# vco.net
KiCad netlist of a schematic drawn in EAGLE
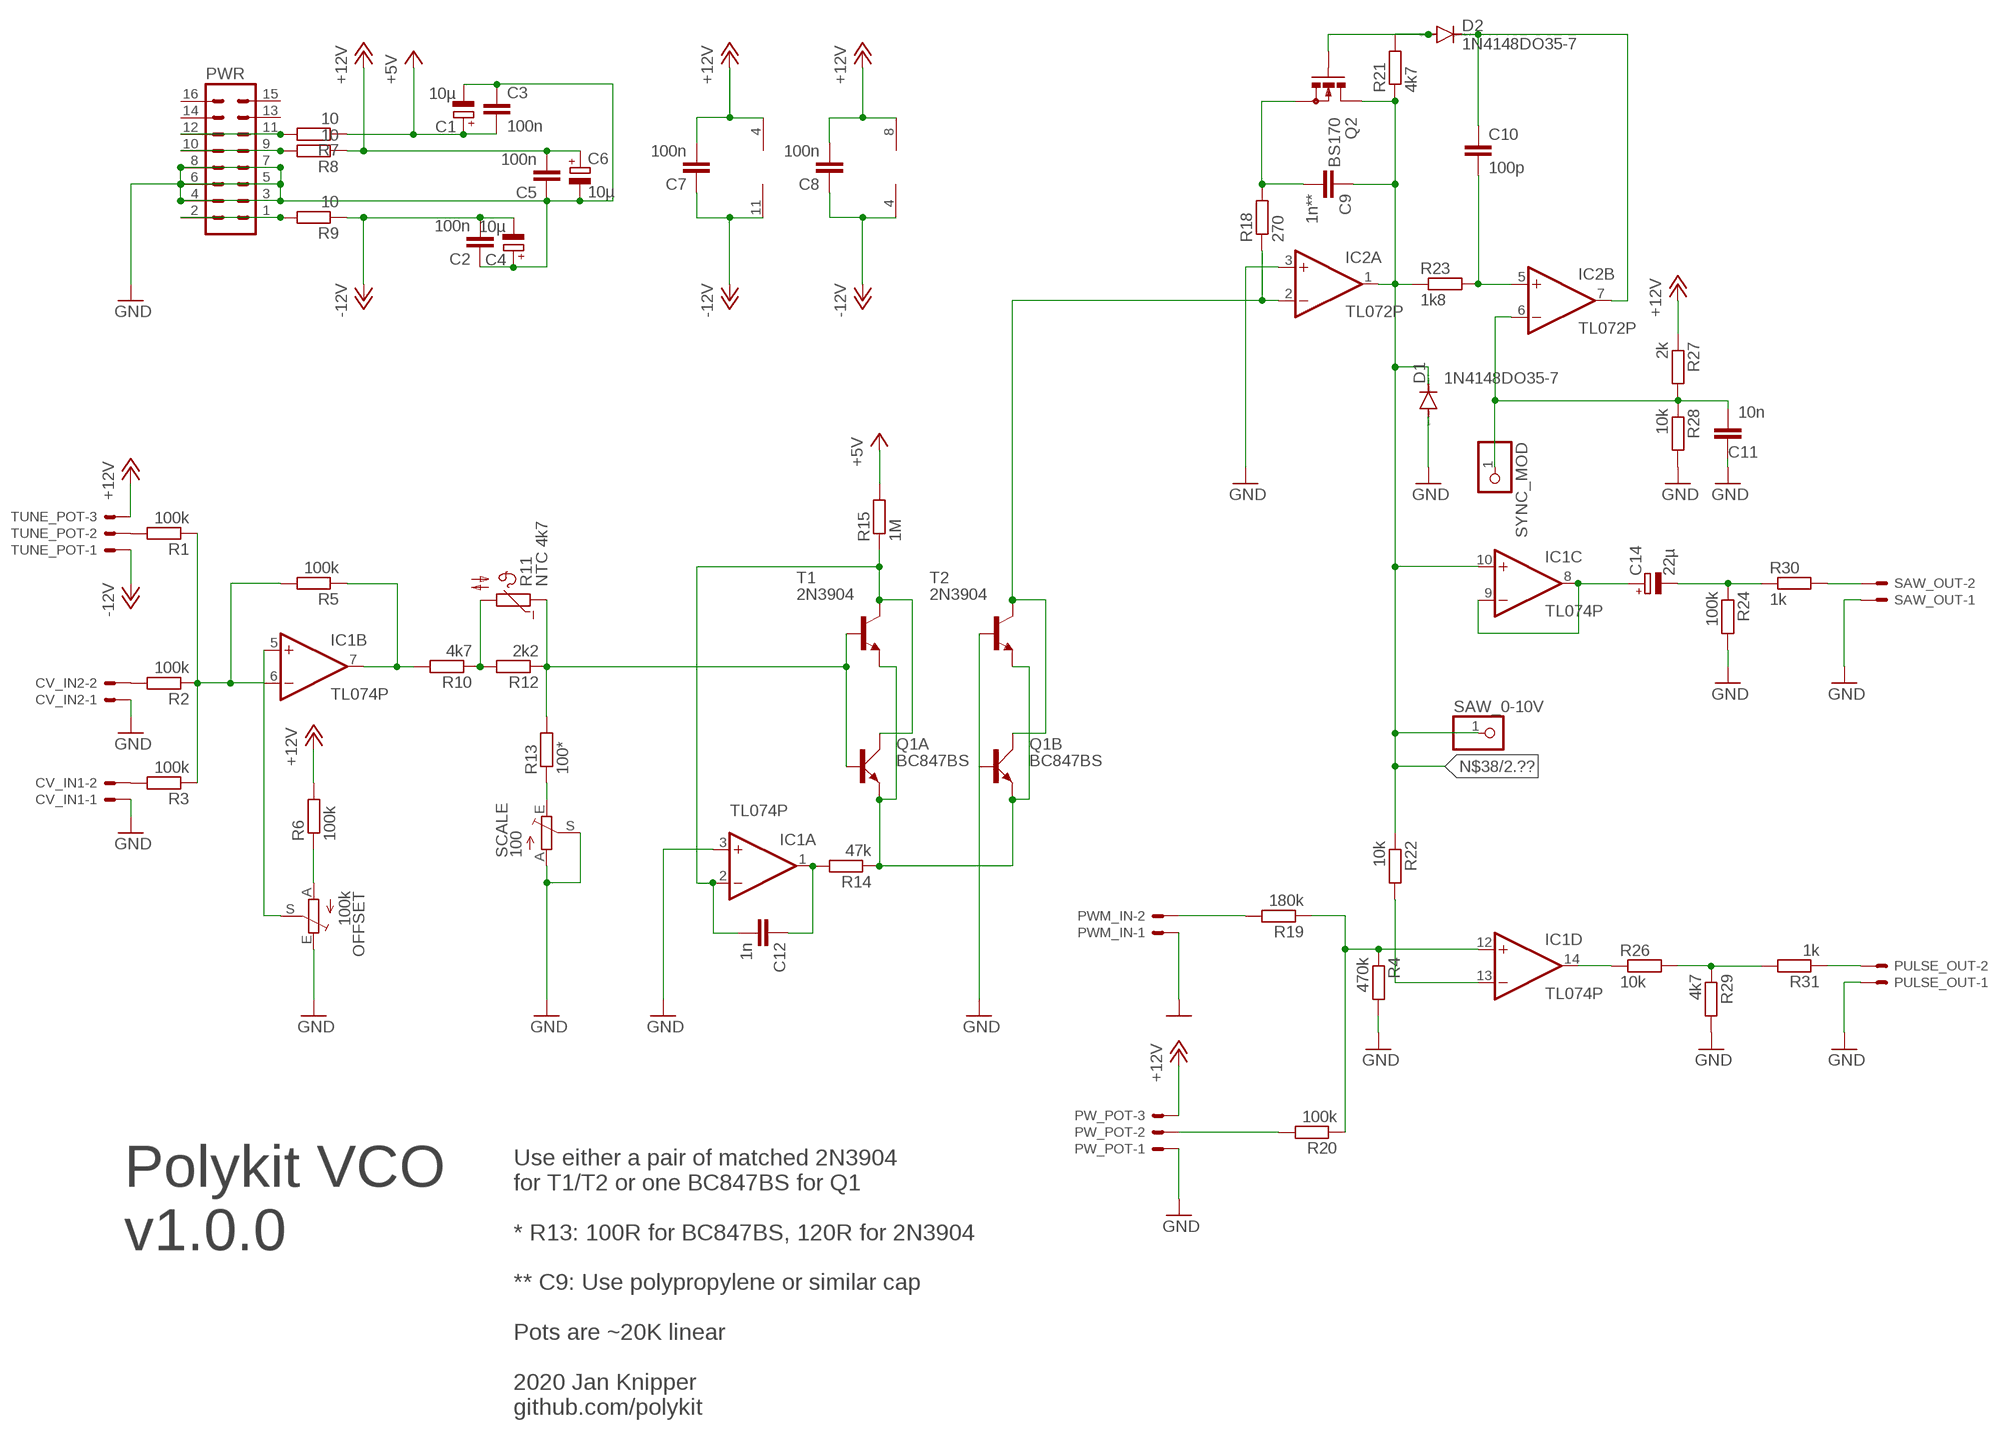
[diagram p0: schematic, sheet 1]
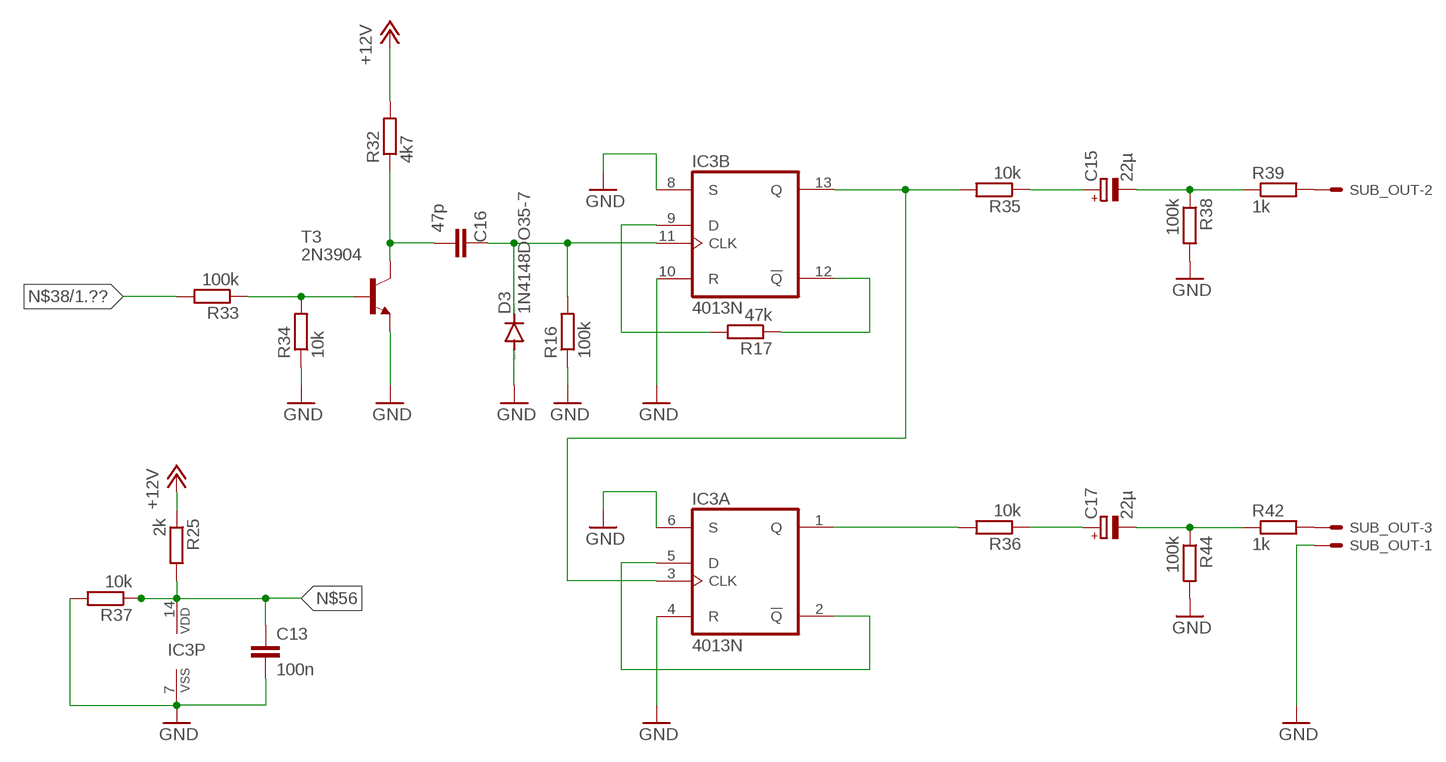
[diagram p1: schematic, sheet 2]

(export (version "E")
  (design (tool "Eeschema 10.0.6"))
  (components
    (comp (ref "C1")
      (value "10µ")
      (footprint "eagle-import:E2,5-5")
      (libsource (lib "eagle-import") (part "CPOL-EUE2.5-5"))
    )
    (comp (ref "C2")
      (value "100n")
      (footprint "eagle-import:C050-030X075")
      (libsource (lib "eagle-import") (part "C-EU050-030X075"))
    )
    (comp (ref "C3")
      (value "100n")
      (footprint "eagle-import:C050-030X075")
      (libsource (lib "eagle-import") (part "C-EU050-030X075"))
    )
    (comp (ref "C4")
      (value "10µ")
      (footprint "eagle-import:E2,5-5")
      (libsource (lib "eagle-import") (part "CPOL-EUE2.5-5"))
    )
    (comp (ref "C5")
      (value "100n")
      (footprint "eagle-import:C050-030X075")
      (libsource (lib "eagle-import") (part "C-EU050-030X075"))
    )
    (comp (ref "C6")
      (value "10µ")
      (footprint "eagle-import:E2,5-5")
      (libsource (lib "eagle-import") (part "CPOL-EUE2.5-5"))
    )
    (comp (ref "C7")
      (value "100n")
      (footprint "eagle-import:C050-030X075")
      (libsource (lib "eagle-import") (part "C-EU050-030X075"))
    )
    (comp (ref "C8")
      (value "100n")
      (footprint "eagle-import:C050-030X075")
      (libsource (lib "eagle-import") (part "C-EU050-030X075"))
    )
    (comp (ref "C9")
      (value "1n**")
      (footprint "eagle-import:C050-030X075")
      (libsource (lib "eagle-import") (part "C-EU050-030X075"))
    )
    (comp (ref "C10")
      (value "100p")
      (footprint "eagle-import:C050-030X075")
      (libsource (lib "eagle-import") (part "C-EU050-030X075"))
    )
    (comp (ref "C11")
      (value "10n")
      (footprint "eagle-import:C050-030X075")
      (libsource (lib "eagle-import") (part "C-EU050-030X075"))
    )
    (comp (ref "C12")
      (value "1n")
      (footprint "eagle-import:C050-024X044")
      (libsource (lib "eagle-import") (part "C-EU050-024X044"))
    )
    (comp (ref "C14")
      (value "22µ")
      (footprint "eagle-import:E2,5-5")
      (libsource (lib "eagle-import") (part "CPOL-EUE2.5-5"))
    )
    (comp (ref "CV_IN1")
      (value "22-23-2021")
      (footprint "eagle-import:22-23-2021")
      (fields (field (name "MF") "MOLEX"))
      (libsource (lib "eagle-import") (part "22-23-2021"))
    )
    (comp (ref "CV_IN2")
      (value "22-23-2021")
      (footprint "eagle-import:22-23-2021")
      (fields (field (name "MF") "MOLEX"))
      (libsource (lib "eagle-import") (part "22-23-2021"))
    )
    (comp (ref "D1")
      (value "1N4148DO35-7")
      (footprint "eagle-import:DO35-7")
      (libsource (lib "eagle-import") (part "1N4148DO35-7"))
    )
    (comp (ref "D2")
      (value "1N4148DO35-7")
      (footprint "eagle-import:DO35-7")
      (libsource (lib "eagle-import") (part "1N4148DO35-7"))
    )
    (comp (ref "IC1")
      (value "TL074P")
      (footprint "eagle-import:DIL14")
      (libsource (lib "eagle-import") (part "TL074P"))
    )
    (comp (ref "IC2")
      (value "TL072P")
      (footprint "eagle-import:DIL08")
      (libsource (lib "eagle-import") (part "TL072P"))
    )
    (comp (ref "OFFSET")
      (value "100k")
      (footprint "eagle-import:S64YW")
      (libsource (lib "eagle-import") (part "TRIM_1234-S64YW"))
    )
    (comp (ref "PULSE_OUT")
      (value "22-23-2021")
      (footprint "eagle-import:22-23-2021")
      (fields (field (name "MF") "MOLEX"))
      (libsource (lib "eagle-import") (part "22-23-2021"))
    )
    (comp (ref "PWM_IN")
      (value "22-23-2021")
      (footprint "eagle-import:22-23-2021")
      (fields (field (name "MF") "MOLEX"))
      (libsource (lib "eagle-import") (part "22-23-2021"))
    )
    (comp (ref "PWR")
      (value "ML16")
      (footprint "eagle-import:ML16")
      (libsource (lib "eagle-import") (part "ML16"))
    )
    (comp (ref "PW_POT")
      (value "22-23-2031")
      (footprint "eagle-import:22-23-2031")
      (fields (field (name "MF") "MOLEX"))
      (libsource (lib "eagle-import") (part "22-23-2031"))
    )
    (comp (ref "Q1")
      (value "BC847BS")
      (footprint "eagle-import:SOT363_PHILIPS")
      (libsource (lib "eagle-import") (part "BC847BS"))
    )
    (comp (ref "Q2")
      (value "BS170")
      (footprint "eagle-import:SOT54E")
      (libsource (lib "eagle-import") (part "BS170"))
    )
    (comp (ref "R1")
      (value "100k")
      (footprint "eagle-import:0207_7")
      (libsource (lib "eagle-import") (part "R-EU_0207/7"))
    )
    (comp (ref "R2")
      (value "100k")
      (footprint "eagle-import:0207_7")
      (libsource (lib "eagle-import") (part "R-EU_0207/7"))
    )
    (comp (ref "R3")
      (value "100k")
      (footprint "eagle-import:0207_7")
      (libsource (lib "eagle-import") (part "R-EU_0207/7"))
    )
    (comp (ref "R4")
      (value "470k")
      (footprint "eagle-import:0207_7")
      (libsource (lib "eagle-import") (part "R-EU_0207/7"))
    )
    (comp (ref "R5")
      (value "100k")
      (footprint "eagle-import:0207_7")
      (libsource (lib "eagle-import") (part "R-EU_0207/7"))
    )
    (comp (ref "R6")
      (value "100k")
      (footprint "eagle-import:0207_7")
      (libsource (lib "eagle-import") (part "R-EU_0207/7"))
    )
    (comp (ref "R7")
      (value "10")
      (footprint "eagle-import:0207_7")
      (libsource (lib "eagle-import") (part "R-EU_0207/7"))
    )
    (comp (ref "R8")
      (value "10")
      (footprint "eagle-import:0207_7")
      (libsource (lib "eagle-import") (part "R-EU_0207/7"))
    )
    (comp (ref "R9")
      (value "10")
      (footprint "eagle-import:0207_7")
      (libsource (lib "eagle-import") (part "R-EU_0207/7"))
    )
    (comp (ref "R10")
      (value "4k7")
      (footprint "eagle-import:0207_7")
      (libsource (lib "eagle-import") (part "R-EU_0207/7"))
    )
    (comp (ref "R11")
      (value "NTC 4k7")
      (footprint "eagle-import:P640")
      (libsource (lib "eagle-import") (part "NTC640"))
    )
    (comp (ref "R12")
      (value "2k2")
      (footprint "eagle-import:0207_7")
      (libsource (lib "eagle-import") (part "R-EU_0207/7"))
    )
    (comp (ref "R13")
      (value "100*")
      (footprint "eagle-import:0207_7")
      (libsource (lib "eagle-import") (part "R-EU_0207/7"))
    )
    (comp (ref "R14")
      (value "47k")
      (footprint "eagle-import:0207_7")
      (libsource (lib "eagle-import") (part "R-EU_0207/7"))
    )
    (comp (ref "R15")
      (value "1M")
      (footprint "eagle-import:0207_7")
      (libsource (lib "eagle-import") (part "R-EU_0207/7"))
    )
    (comp (ref "R18")
      (value "270")
      (footprint "eagle-import:0207_7")
      (libsource (lib "eagle-import") (part "R-EU_0207/7"))
    )
    (comp (ref "R19")
      (value "180k")
      (footprint "eagle-import:0207_7")
      (libsource (lib "eagle-import") (part "R-EU_0207/7"))
    )
    (comp (ref "R20")
      (value "100k")
      (footprint "eagle-import:0207_7")
      (libsource (lib "eagle-import") (part "R-EU_0207/7"))
    )
    (comp (ref "R21")
      (value "4k7")
      (footprint "eagle-import:0207_7")
      (libsource (lib "eagle-import") (part "R-EU_0207/7"))
    )
    (comp (ref "R22")
      (value "10k")
      (footprint "eagle-import:0207_7")
      (libsource (lib "eagle-import") (part "R-EU_0207/7"))
    )
    (comp (ref "R23")
      (value "1k8")
      (footprint "eagle-import:0207_7")
      (libsource (lib "eagle-import") (part "R-EU_0207/7"))
    )
    (comp (ref "R24")
      (value "100k")
      (footprint "eagle-import:0207_7")
      (libsource (lib "eagle-import") (part "R-EU_0207/7"))
    )
    (comp (ref "R26")
      (value "10k")
      (footprint "eagle-import:0207_7")
      (libsource (lib "eagle-import") (part "R-EU_0207/7"))
    )
    (comp (ref "R27")
      (value "2k")
      (footprint "eagle-import:0207_7")
      (libsource (lib "eagle-import") (part "R-EU_0207/7"))
    )
    (comp (ref "R28")
      (value "10k")
      (footprint "eagle-import:0207_7")
      (libsource (lib "eagle-import") (part "R-EU_0207/7"))
    )
    (comp (ref "R29")
      (value "4k7")
      (footprint "eagle-import:0207_7")
      (libsource (lib "eagle-import") (part "R-EU_0207/7"))
    )
    (comp (ref "R30")
      (value "1k")
      (footprint "eagle-import:0207_7")
      (libsource (lib "eagle-import") (part "R-EU_0207/7"))
    )
    (comp (ref "R31")
      (value "1k")
      (footprint "eagle-import:0207_7")
      (libsource (lib "eagle-import") (part "R-EU_0207/7"))
    )
    (comp (ref "SAW_0-10V")
      (value "PINHD-1X1")
      (footprint "eagle-import:1X01")
      (libsource (lib "eagle-import") (part "PINHD-1X1"))
    )
    (comp (ref "SAW_OUT")
      (value "22-23-2021")
      (footprint "eagle-import:22-23-2021")
      (fields (field (name "MF") "MOLEX"))
      (libsource (lib "eagle-import") (part "22-23-2021"))
    )
    (comp (ref "SCALE")
      (value "100")
      (footprint "eagle-import:S64YW")
      (libsource (lib "eagle-import") (part "TRIM_1234-S64YW"))
    )
    (comp (ref "SYNC_MOD")
      (value "PINHD-1X1")
      (footprint "eagle-import:1X01")
      (libsource (lib "eagle-import") (part "PINHD-1X1"))
    )
    (comp (ref "T1")
      (value "2N3904")
      (footprint "eagle-import:TO92")
      (libsource (lib "eagle-import") (part "2N3904"))
    )
    (comp (ref "T2")
      (value "2N3904")
      (footprint "eagle-import:TO92")
      (libsource (lib "eagle-import") (part "2N3904"))
    )
    (comp (ref "TUNE_POT")
      (value "22-23-2031")
      (footprint "eagle-import:22-23-2031")
      (fields (field (name "MF") "MOLEX"))
      (libsource (lib "eagle-import") (part "22-23-2031"))
    )
    (comp (ref "C13")
      (value "100n")
      (footprint "eagle-import:C050-030X075")
      (libsource (lib "eagle-import") (part "C-EU050-030X075"))
    )
    (comp (ref "C15")
      (value "22µ")
      (footprint "eagle-import:E2,5-5")
      (libsource (lib "eagle-import") (part "CPOL-EUE2.5-5"))
    )
    (comp (ref "C16")
      (value "47p")
      (footprint "eagle-import:C050-030X075")
      (libsource (lib "eagle-import") (part "C-EU050-030X075"))
    )
    (comp (ref "C17")
      (value "22µ")
      (footprint "eagle-import:E2,5-5")
      (libsource (lib "eagle-import") (part "CPOL-EUE2.5-5"))
    )
    (comp (ref "D3")
      (value "1N4148DO35-7")
      (footprint "eagle-import:DO35-7")
      (libsource (lib "eagle-import") (part "1N4148DO35-7"))
    )
    (comp (ref "IC3")
      (value "4013N")
      (footprint "eagle-import:DIL14")
      (libsource (lib "eagle-import") (part "4013N"))
    )
    (comp (ref "R16")
      (value "100k")
      (footprint "eagle-import:0207_7")
      (libsource (lib "eagle-import") (part "R-EU_0207/7"))
    )
    (comp (ref "R17")
      (value "47k")
      (footprint "eagle-import:0207_7")
      (libsource (lib "eagle-import") (part "R-EU_0207/7"))
    )
    (comp (ref "R25")
      (value "2k")
      (footprint "eagle-import:0207_7")
      (libsource (lib "eagle-import") (part "R-EU_0207/7"))
    )
    (comp (ref "R32")
      (value "4k7")
      (footprint "eagle-import:0207_7")
      (libsource (lib "eagle-import") (part "R-EU_0207/7"))
    )
    (comp (ref "R33")
      (value "100k")
      (footprint "eagle-import:0207_7")
      (libsource (lib "eagle-import") (part "R-EU_0207/7"))
    )
    (comp (ref "R34")
      (value "10k")
      (footprint "eagle-import:0207_7")
      (libsource (lib "eagle-import") (part "R-EU_0207/7"))
    )
    (comp (ref "R35")
      (value "10k")
      (footprint "eagle-import:0207_7")
      (libsource (lib "eagle-import") (part "R-EU_0207/7"))
    )
    (comp (ref "R36")
      (value "10k")
      (footprint "eagle-import:0207_7")
      (libsource (lib "eagle-import") (part "R-EU_0207/7"))
    )
    (comp (ref "R37")
      (value "10k")
      (footprint "eagle-import:0207_7")
      (libsource (lib "eagle-import") (part "R-EU_0207/7"))
    )
    (comp (ref "R38")
      (value "100k")
      (footprint "eagle-import:0207_7")
      (libsource (lib "eagle-import") (part "R-EU_0207/7"))
    )
    (comp (ref "R39")
      (value "1k")
      (footprint "eagle-import:0207_7")
      (libsource (lib "eagle-import") (part "R-EU_0207/7"))
    )
    (comp (ref "R42")
      (value "1k")
      (footprint "eagle-import:0207_7")
      (libsource (lib "eagle-import") (part "R-EU_0207/7"))
    )
    (comp (ref "R44")
      (value "100k")
      (footprint "eagle-import:0207_7")
      (libsource (lib "eagle-import") (part "R-EU_0207/7"))
    )
    (comp (ref "SUB_OUT")
      (value "22-23-2031")
      (footprint "eagle-import:22-23-2031")
      (fields (field (name "MF") "MOLEX"))
      (libsource (lib "eagle-import") (part "22-23-2031"))
    )
    (comp (ref "T3")
      (value "2N3904")
      (footprint "eagle-import:TO92")
      (libsource (lib "eagle-import") (part "2N3904"))
    )
  )
  (nets
    (net (code "1") (name "+5V") (class "Default")
      (node (ref "C1") (pin "+") (pinfunction "+_+") (pintype "passive"))
      (node (ref "C3") (pin "2") (pinfunction "2_2") (pintype "passive"))
      (node (ref "R15") (pin "2") (pinfunction "2_2") (pintype "passive"))
      (node (ref "R7") (pin "1") (pinfunction "1_1") (pintype "passive"))
    )
    (net (code "2") (name "+12V") (class "Default")
      (node (ref "C5") (pin "2") (pinfunction "2_2") (pintype "passive"))
      (node (ref "C6") (pin "+") (pinfunction "+_+") (pintype "passive"))
      (node (ref "C7") (pin "2") (pinfunction "2_2") (pintype "passive"))
      (node (ref "C8") (pin "2") (pinfunction "2_2") (pintype "passive"))
      (node (ref "IC1") (pin "4") (pinfunction "V+_4") (pintype "power_in"))
      (node (ref "IC2") (pin "8") (pinfunction "V+_8") (pintype "power_in"))
      (node (ref "PW_POT") (pin "3") (pinfunction "S_3") (pintype "passive"))
      (node (ref "R25") (pin "1") (pinfunction "1_1") (pintype "passive"))
      (node (ref "R27") (pin "1") (pinfunction "1_1") (pintype "passive"))
      (node (ref "R32") (pin "2") (pinfunction "2_2") (pintype "passive"))
      (node (ref "R6") (pin "2") (pinfunction "2_2") (pintype "passive"))
      (node (ref "R8") (pin "1") (pinfunction "1_1") (pintype "passive"))
      (node (ref "TUNE_POT") (pin "3") (pinfunction "S_3") (pintype "passive"))
    )
    (net (code "3") (name "-12V") (class "Default")
      (node (ref "C2") (pin "2") (pinfunction "2_2") (pintype "passive"))
      (node (ref "C4") (pin "-") (pinfunction "-_-") (pintype "passive"))
      (node (ref "C7") (pin "1") (pinfunction "1_1") (pintype "passive"))
      (node (ref "C8") (pin "1") (pinfunction "1_1") (pintype "passive"))
      (node (ref "IC1") (pin "11") (pinfunction "V-_11") (pintype "power_in"))
      (node (ref "IC2") (pin "4") (pinfunction "V-_4") (pintype "power_in"))
      (node (ref "R9") (pin "1") (pinfunction "1_1") (pintype "passive"))
      (node (ref "TUNE_POT") (pin "1") (pinfunction "S_1") (pintype "passive"))
    )
    (net (code "4") (name "GND") (class "Default")
      (node (ref "C1") (pin "-") (pinfunction "-_-") (pintype "passive"))
      (node (ref "C11") (pin "1") (pinfunction "1_1") (pintype "passive"))
      (node (ref "C13") (pin "2") (pinfunction "2_2") (pintype "passive"))
      (node (ref "C2") (pin "1") (pinfunction "1_1") (pintype "passive"))
      (node (ref "C3") (pin "1") (pinfunction "1_1") (pintype "passive"))
      (node (ref "C4") (pin "+") (pinfunction "+_+") (pintype "passive"))
      (node (ref "C5") (pin "1") (pinfunction "1_1") (pintype "passive"))
      (node (ref "C6") (pin "-") (pinfunction "-_-") (pintype "passive"))
      (node (ref "CV_IN1") (pin "1") (pinfunction "S_1") (pintype "passive"))
      (node (ref "CV_IN2") (pin "1") (pinfunction "S_1") (pintype "passive"))
      (node (ref "D1") (pin "A") (pinfunction "A_A") (pintype "passive"))
      (node (ref "D3") (pin "A") (pinfunction "A_A") (pintype "passive"))
      (node (ref "IC1") (pin "3") (pinfunction "+IN_3") (pintype "input"))
      (node (ref "IC2") (pin "3") (pinfunction "+IN_3") (pintype "input"))
      (node (ref "IC3") (pin "10") (pinfunction "R_10") (pintype "input"))
      (node (ref "IC3") (pin "4") (pinfunction "R_4") (pintype "input"))
      (node (ref "IC3") (pin "6") (pinfunction "S_6") (pintype "input"))
      (node (ref "IC3") (pin "7") (pinfunction "VSS_7") (pintype "power_in"))
      (node (ref "IC3") (pin "8") (pinfunction "S_8") (pintype "input"))
      (node (ref "OFFSET") (pin "E") (pinfunction "E_E") (pintype "passive"))
      (node (ref "PULSE_OUT") (pin "1") (pinfunction "S_1") (pintype "passive"))
      (node (ref "PWM_IN") (pin "1") (pinfunction "S_1") (pintype "passive"))
      (node (ref "PWR") (pin "3") (pinfunction "3_3") (pintype "passive"))
      (node (ref "PWR") (pin "4") (pinfunction "4_4") (pintype "passive"))
      (node (ref "PWR") (pin "5") (pinfunction "5_5") (pintype "passive"))
      (node (ref "PWR") (pin "6") (pinfunction "6_6") (pintype "passive"))
      (node (ref "PWR") (pin "7") (pinfunction "7_7") (pintype "passive"))
      (node (ref "PWR") (pin "8") (pinfunction "8_8") (pintype "passive"))
      (node (ref "PW_POT") (pin "1") (pinfunction "S_1") (pintype "passive"))
      (node (ref "Q1") (pin "5") (pinfunction "B_5") (pintype "passive"))
      (node (ref "R16") (pin "1") (pinfunction "1_1") (pintype "passive"))
      (node (ref "R24") (pin "2") (pinfunction "2_2") (pintype "passive"))
      (node (ref "R28") (pin "2") (pinfunction "2_2") (pintype "passive"))
      (node (ref "R29") (pin "2") (pinfunction "2_2") (pintype "passive"))
      (node (ref "R34") (pin "1") (pinfunction "1_1") (pintype "passive"))
      (node (ref "R37") (pin "2") (pinfunction "2_2") (pintype "passive"))
      (node (ref "R38") (pin "2") (pinfunction "2_2") (pintype "passive"))
      (node (ref "R4") (pin "2") (pinfunction "2_2") (pintype "passive"))
      (node (ref "R44") (pin "2") (pinfunction "2_2") (pintype "passive"))
      (node (ref "SAW_OUT") (pin "1") (pinfunction "S_1") (pintype "passive"))
      (node (ref "SCALE") (pin "A") (pinfunction "A_A") (pintype "passive"))
      (node (ref "SCALE") (pin "S") (pinfunction "S_S") (pintype "passive"))
      (node (ref "SUB_OUT") (pin "1") (pinfunction "S_1") (pintype "passive"))
      (node (ref "T2") (pin "2") (pinfunction "B_2") (pintype "passive"))
      (node (ref "T3") (pin "3") (pinfunction "E_3") (pintype "passive"))
    )
    (net (code "5") (name "N$38") (class "Default")
      (node (ref "C9") (pin "1") (pinfunction "1_1") (pintype "passive"))
      (node (ref "D1") (pin "C") (pinfunction "C_C") (pintype "passive"))
      (node (ref "IC1") (pin "10") (pinfunction "+IN_10") (pintype "input"))
      (node (ref "IC2") (pin "1") (pinfunction "OUT_1") (pintype "output"))
      (node (ref "Q2") (pin "D") (pinfunction "D_D") (pintype "passive"))
      (node (ref "R21") (pin "1") (pinfunction "1_1") (pintype "passive"))
      (node (ref "R22") (pin "1") (pinfunction "1_1") (pintype "passive"))
      (node (ref "R23") (pin "1") (pinfunction "1_1") (pintype "passive"))
      (node (ref "R33") (pin "2") (pinfunction "2_2") (pintype "passive"))
      (node (ref "SAW_0-10V") (pin "1") (pinfunction "1_1") (pintype "passive"))
    )
    (net (code "6") (name "N$56") (class "Default")
      (node (ref "C13") (pin "1") (pinfunction "1_1") (pintype "passive"))
      (node (ref "IC3") (pin "14") (pinfunction "VDD_14") (pintype "power_in"))
      (node (ref "R25") (pin "2") (pinfunction "2_2") (pintype "passive"))
      (node (ref "R37") (pin "1") (pinfunction "1_1") (pintype "passive"))
    )
    (net (code "7") (name "Net-(C9-Pad2)") (class "Default")
      (node (ref "C9") (pin "2") (pinfunction "2_2") (pintype "passive"))
      (node (ref "Q2") (pin "S") (pinfunction "S_S") (pintype "passive"))
      (node (ref "R18") (pin "2") (pinfunction "2_2") (pintype "passive"))
    )
    (net (code "8") (name "Net-(C14-Pad-)") (class "Default")
      (node (ref "C14") (pin "-") (pinfunction "-_-") (pintype "passive"))
      (node (ref "R24") (pin "1") (pinfunction "1_1") (pintype "passive"))
      (node (ref "R30") (pin "1") (pinfunction "1_1") (pintype "passive"))
    )
    (net (code "9") (name "Net-(C15-Pad+)") (class "Default")
      (node (ref "C15") (pin "+") (pinfunction "+_+") (pintype "passive"))
      (node (ref "R35") (pin "1") (pinfunction "1_1") (pintype "passive"))
    )
    (net (code "10") (name "Net-(C15-Pad-)") (class "Default")
      (node (ref "C15") (pin "-") (pinfunction "-_-") (pintype "passive"))
      (node (ref "R38") (pin "1") (pinfunction "1_1") (pintype "passive"))
      (node (ref "R39") (pin "1") (pinfunction "1_1") (pintype "passive"))
    )
    (net (code "11") (name "Net-(C17-Pad+)") (class "Default")
      (node (ref "C17") (pin "+") (pinfunction "+_+") (pintype "passive"))
      (node (ref "R36") (pin "1") (pinfunction "1_1") (pintype "passive"))
    )
    (net (code "12") (name "Net-(C17-Pad-)") (class "Default")
      (node (ref "C17") (pin "-") (pinfunction "-_-") (pintype "passive"))
      (node (ref "R42") (pin "1") (pinfunction "1_1") (pintype "passive"))
      (node (ref "R44") (pin "1") (pinfunction "1_1") (pintype "passive"))
    )
    (net (code "13") (name "Net-(CV_IN1B-S)") (class "Default")
      (node (ref "CV_IN1") (pin "2") (pinfunction "S_2") (pintype "passive"))
      (node (ref "R3") (pin "2") (pinfunction "2_2") (pintype "passive"))
    )
    (net (code "14") (name "Net-(CV_IN2B-S)") (class "Default")
      (node (ref "CV_IN2") (pin "2") (pinfunction "S_2") (pintype "passive"))
      (node (ref "R2") (pin "2") (pinfunction "2_2") (pintype "passive"))
    )
    (net (code "15") (name "Net-(D2-PadA)") (class "Default")
      (node (ref "D2") (pin "A") (pinfunction "A_A") (pintype "passive"))
      (node (ref "Q2") (pin "G") (pinfunction "G_G") (pintype "passive"))
      (node (ref "R21") (pin "2") (pinfunction "2_2") (pintype "passive"))
    )
    (net (code "16") (name "Net-(IC1A--IN)") (class "Default")
      (node (ref "C12") (pin "2") (pinfunction "2_2") (pintype "passive"))
      (node (ref "IC1") (pin "2") (pinfunction "-IN_2") (pintype "input"))
      (node (ref "Q1") (pin "6") (pinfunction "C_6") (pintype "passive"))
      (node (ref "R15") (pin "1") (pinfunction "1_1") (pintype "passive"))
      (node (ref "T1") (pin "1") (pinfunction "C_1") (pintype "passive"))
    )
    (net (code "17") (name "Net-(IC1A-OUT)") (class "Default")
      (node (ref "C12") (pin "1") (pinfunction "1_1") (pintype "passive"))
      (node (ref "IC1") (pin "1") (pinfunction "OUT_1") (pintype "output"))
      (node (ref "R14") (pin "2") (pinfunction "2_2") (pintype "passive"))
    )
    (net (code "18") (name "Net-(IC1B-+IN)") (class "Default")
      (node (ref "IC1") (pin "5") (pinfunction "+IN_5") (pintype "input"))
      (node (ref "OFFSET") (pin "S") (pinfunction "S_S") (pintype "passive"))
    )
    (net (code "19") (name "Net-(IC1B--IN)") (class "Default")
      (node (ref "IC1") (pin "6") (pinfunction "-IN_6") (pintype "input"))
      (node (ref "R1") (pin "1") (pinfunction "1_1") (pintype "passive"))
      (node (ref "R2") (pin "1") (pinfunction "1_1") (pintype "passive"))
      (node (ref "R3") (pin "1") (pinfunction "1_1") (pintype "passive"))
      (node (ref "R5") (pin "2") (pinfunction "2_2") (pintype "passive"))
    )
    (net (code "20") (name "Net-(IC1B-OUT)") (class "Default")
      (node (ref "IC1") (pin "7") (pinfunction "OUT_7") (pintype "output"))
      (node (ref "R10") (pin "2") (pinfunction "2_2") (pintype "passive"))
      (node (ref "R5") (pin "1") (pinfunction "1_1") (pintype "passive"))
    )
    (net (code "21") (name "Net-(IC1C--IN)") (class "Default")
      (node (ref "C14") (pin "+") (pinfunction "+_+") (pintype "passive"))
      (node (ref "IC1") (pin "8") (pinfunction "OUT_8") (pintype "output"))
      (node (ref "IC1") (pin "9") (pinfunction "-IN_9") (pintype "input"))
    )
    (net (code "22") (name "Net-(IC1D-+IN)") (class "Default")
      (node (ref "IC1") (pin "12") (pinfunction "+IN_12") (pintype "input"))
      (node (ref "R19") (pin "1") (pinfunction "1_1") (pintype "passive"))
      (node (ref "R20") (pin "1") (pinfunction "1_1") (pintype "passive"))
      (node (ref "R4") (pin "1") (pinfunction "1_1") (pintype "passive"))
    )
    (net (code "23") (name "Net-(IC1D--IN)") (class "Default")
      (node (ref "IC1") (pin "13") (pinfunction "-IN_13") (pintype "input"))
      (node (ref "R22") (pin "2") (pinfunction "2_2") (pintype "passive"))
    )
    (net (code "24") (name "Net-(IC1D-OUT)") (class "Default")
      (node (ref "IC1") (pin "14") (pinfunction "OUT_14") (pintype "output"))
      (node (ref "R26") (pin "1") (pinfunction "1_1") (pintype "passive"))
    )
    (net (code "25") (name "Net-(IC2A--IN)") (class "Default")
      (node (ref "IC2") (pin "2") (pinfunction "-IN_2") (pintype "input"))
      (node (ref "Q1") (pin "3") (pinfunction "C_3") (pintype "passive"))
      (node (ref "R18") (pin "1") (pinfunction "1_1") (pintype "passive"))
      (node (ref "T2") (pin "1") (pinfunction "C_1") (pintype "passive"))
    )
    (net (code "26") (name "Net-(IC2B-+IN)") (class "Default")
      (node (ref "C10") (pin "2") (pinfunction "2_2") (pintype "passive"))
      (node (ref "IC2") (pin "5") (pinfunction "+IN_5") (pintype "input"))
      (node (ref "R23") (pin "2") (pinfunction "2_2") (pintype "passive"))
    )
    (net (code "27") (name "Net-(IC2B--IN)") (class "Default")
      (node (ref "C11") (pin "2") (pinfunction "2_2") (pintype "passive"))
      (node (ref "IC2") (pin "6") (pinfunction "-IN_6") (pintype "input"))
      (node (ref "R27") (pin "2") (pinfunction "2_2") (pintype "passive"))
      (node (ref "R28") (pin "1") (pinfunction "1_1") (pintype "passive"))
      (node (ref "SYNC_MOD") (pin "1") (pinfunction "1_1") (pintype "passive"))
    )
    (net (code "28") (name "Net-(IC2B-OUT)") (class "Default")
      (node (ref "C10") (pin "1") (pinfunction "1_1") (pintype "passive"))
      (node (ref "D2") (pin "C") (pinfunction "C_C") (pintype "passive"))
      (node (ref "IC2") (pin "7") (pinfunction "OUT_7") (pintype "output"))
    )
    (net (code "29") (name "Net-(IC3A-CLK)") (class "Default")
      (node (ref "IC3") (pin "13") (pinfunction "Q_13") (pintype "output"))
      (node (ref "IC3") (pin "3") (pinfunction "CLK_3") (pintype "input"))
      (node (ref "R35") (pin "2") (pinfunction "2_2") (pintype "passive"))
    )
    (net (code "30") (name "Net-(IC3A-D)") (class "Default")
      (node (ref "IC3") (pin "2") (pinfunction "~{Q}_2") (pintype "output"))
      (node (ref "IC3") (pin "5") (pinfunction "D_5") (pintype "input"))
    )
    (net (code "31") (name "Net-(IC3A-Q)") (class "Default")
      (node (ref "IC3") (pin "1") (pinfunction "Q_1") (pintype "output"))
      (node (ref "R36") (pin "2") (pinfunction "2_2") (pintype "passive"))
    )
    (net (code "32") (name "Net-(IC3B-CLK)") (class "Default")
      (node (ref "C16") (pin "1") (pinfunction "1_1") (pintype "passive"))
      (node (ref "D3") (pin "C") (pinfunction "C_C") (pintype "passive"))
      (node (ref "IC3") (pin "11") (pinfunction "CLK_11") (pintype "input"))
      (node (ref "R16") (pin "2") (pinfunction "2_2") (pintype "passive"))
    )
    (net (code "33") (name "Net-(IC3B-D)") (class "Default")
      (node (ref "IC3") (pin "9") (pinfunction "D_9") (pintype "input"))
      (node (ref "R17") (pin "2") (pinfunction "2_2") (pintype "passive"))
    )
    (net (code "34") (name "Net-(IC3B-~{Q})") (class "Default")
      (node (ref "IC3") (pin "12") (pinfunction "~{Q}_12") (pintype "output"))
      (node (ref "R17") (pin "1") (pinfunction "1_1") (pintype "passive"))
    )
    (net (code "35") (name "Net-(OFFSET-PadA)") (class "Default")
      (node (ref "OFFSET") (pin "A") (pinfunction "A_A") (pintype "passive"))
      (node (ref "R6") (pin "1") (pinfunction "1_1") (pintype "passive"))
    )
    (net (code "36") (name "Net-(PULSE_OUTB-S)") (class "Default")
      (node (ref "PULSE_OUT") (pin "2") (pinfunction "S_2") (pintype "passive"))
      (node (ref "R31") (pin "1") (pinfunction "1_1") (pintype "passive"))
    )
    (net (code "37") (name "Net-(PWM_INB-S)") (class "Default")
      (node (ref "PWM_IN") (pin "2") (pinfunction "S_2") (pintype "passive"))
      (node (ref "R19") (pin "2") (pinfunction "2_2") (pintype "passive"))
    )
    (net (code "38") (name "Net-(PWR-Pad1)") (class "Default")
      (node (ref "PWR") (pin "1") (pinfunction "1_1") (pintype "passive"))
      (node (ref "PWR") (pin "2") (pinfunction "2_2") (pintype "passive"))
      (node (ref "R9") (pin "2") (pinfunction "2_2") (pintype "passive"))
    )
    (net (code "39") (name "Net-(PWR-Pad10)") (class "Default")
      (node (ref "PWR") (pin "10") (pinfunction "10_10") (pintype "passive"))
      (node (ref "PWR") (pin "9") (pinfunction "9_9") (pintype "passive"))
      (node (ref "R8") (pin "2") (pinfunction "2_2") (pintype "passive"))
    )
    (net (code "40") (name "Net-(PWR-Pad11)") (class "Default")
      (node (ref "PWR") (pin "11") (pinfunction "11_11") (pintype "passive"))
      (node (ref "PWR") (pin "12") (pinfunction "12_12") (pintype "passive"))
      (node (ref "R7") (pin "2") (pinfunction "2_2") (pintype "passive"))
    )
    (net (code "41") (name "Net-(PW_POTB-S)") (class "Default")
      (node (ref "PW_POT") (pin "2") (pinfunction "S_2") (pintype "passive"))
      (node (ref "R20") (pin "2") (pinfunction "2_2") (pintype "passive"))
    )
    (net (code "42") (name "Net-(Q1A-B)") (class "Default")
      (node (ref "Q1") (pin "2") (pinfunction "B_2") (pintype "passive"))
      (node (ref "R11") (pin "1") (pinfunction "1_1") (pintype "passive"))
      (node (ref "R12") (pin "1") (pinfunction "1_1") (pintype "passive"))
      (node (ref "R13") (pin "2") (pinfunction "2_2") (pintype "passive"))
      (node (ref "T1") (pin "2") (pinfunction "B_2") (pintype "passive"))
    )
    (net (code "43") (name "Net-(Q1A-E)") (class "Default")
      (node (ref "Q1") (pin "1") (pinfunction "E_1") (pintype "passive"))
      (node (ref "Q1") (pin "4") (pinfunction "E_4") (pintype "passive"))
      (node (ref "R14") (pin "1") (pinfunction "1_1") (pintype "passive"))
      (node (ref "T1") (pin "3") (pinfunction "E_3") (pintype "passive"))
      (node (ref "T2") (pin "3") (pinfunction "E_3") (pintype "passive"))
    )
    (net (code "44") (name "Net-(R10-Pad1)") (class "Default")
      (node (ref "R10") (pin "1") (pinfunction "1_1") (pintype "passive"))
      (node (ref "R11") (pin "2") (pinfunction "2_2") (pintype "passive"))
      (node (ref "R12") (pin "2") (pinfunction "2_2") (pintype "passive"))
    )
    (net (code "45") (name "Net-(R13-Pad1)") (class "Default")
      (node (ref "R13") (pin "1") (pinfunction "1_1") (pintype "passive"))
      (node (ref "SCALE") (pin "E") (pinfunction "E_E") (pintype "passive"))
    )
    (net (code "46") (name "Net-(R26-Pad2)") (class "Default")
      (node (ref "R26") (pin "2") (pinfunction "2_2") (pintype "passive"))
      (node (ref "R29") (pin "1") (pinfunction "1_1") (pintype "passive"))
      (node (ref "R31") (pin "2") (pinfunction "2_2") (pintype "passive"))
    )
    (net (code "47") (name "Net-(SAW_OUTB-S)") (class "Default")
      (node (ref "R30") (pin "2") (pinfunction "2_2") (pintype "passive"))
      (node (ref "SAW_OUT") (pin "2") (pinfunction "S_2") (pintype "passive"))
    )
    (net (code "48") (name "Net-(SUB_OUTB-S)") (class "Default")
      (node (ref "R39") (pin "2") (pinfunction "2_2") (pintype "passive"))
      (node (ref "SUB_OUT") (pin "2") (pinfunction "S_2") (pintype "passive"))
    )
    (net (code "49") (name "Net-(SUB_OUTC-S)") (class "Default")
      (node (ref "R42") (pin "2") (pinfunction "2_2") (pintype "passive"))
      (node (ref "SUB_OUT") (pin "3") (pinfunction "S_3") (pintype "passive"))
    )
    (net (code "50") (name "Net-(T3-B)") (class "Default")
      (node (ref "R33") (pin "1") (pinfunction "1_1") (pintype "passive"))
      (node (ref "R34") (pin "2") (pinfunction "2_2") (pintype "passive"))
      (node (ref "T3") (pin "2") (pinfunction "B_2") (pintype "passive"))
    )
    (net (code "51") (name "Net-(T3-C)") (class "Default")
      (node (ref "C16") (pin "2") (pinfunction "2_2") (pintype "passive"))
      (node (ref "R32") (pin "1") (pinfunction "1_1") (pintype "passive"))
      (node (ref "T3") (pin "1") (pinfunction "C_1") (pintype "passive"))
    )
    (net (code "52") (name "Net-(TUNE_POTB-S)") (class "Default")
      (node (ref "R1") (pin "2") (pinfunction "2_2") (pintype "passive"))
      (node (ref "TUNE_POT") (pin "2") (pinfunction "S_2") (pintype "passive"))
    )
    (net (code "53") (name "unconnected-(OFFSET-S-PadS@1)") (class "Default")
      (node (ref "OFFSET") (pin "S@1") (pinfunction "S_S@1") (pintype "passive"))
    )
    (net (code "54") (name "unconnected-(PWR-Pad13)") (class "Default")
      (node (ref "PWR") (pin "13") (pinfunction "13_13") (pintype "passive"))
    )
    (net (code "55") (name "unconnected-(PWR-Pad14)") (class "Default")
      (node (ref "PWR") (pin "14") (pinfunction "14_14") (pintype "passive"))
    )
    (net (code "56") (name "unconnected-(PWR-Pad15)") (class "Default")
      (node (ref "PWR") (pin "15") (pinfunction "15_15") (pintype "passive"))
    )
    (net (code "57") (name "unconnected-(PWR-Pad16)") (class "Default")
      (node (ref "PWR") (pin "16") (pinfunction "16_16") (pintype "passive"))
    )
    (net (code "58") (name "unconnected-(SCALE-S-PadS@1)") (class "Default")
      (node (ref "SCALE") (pin "S@1") (pinfunction "S_S@1") (pintype "passive"))
    )
  )
)
